# Etch-a-sketch.net
KiCad netlist of a schematic drawn in EAGLE
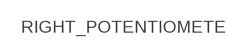
[diagram p0: schematic, sheet 1, part 1 of 2]
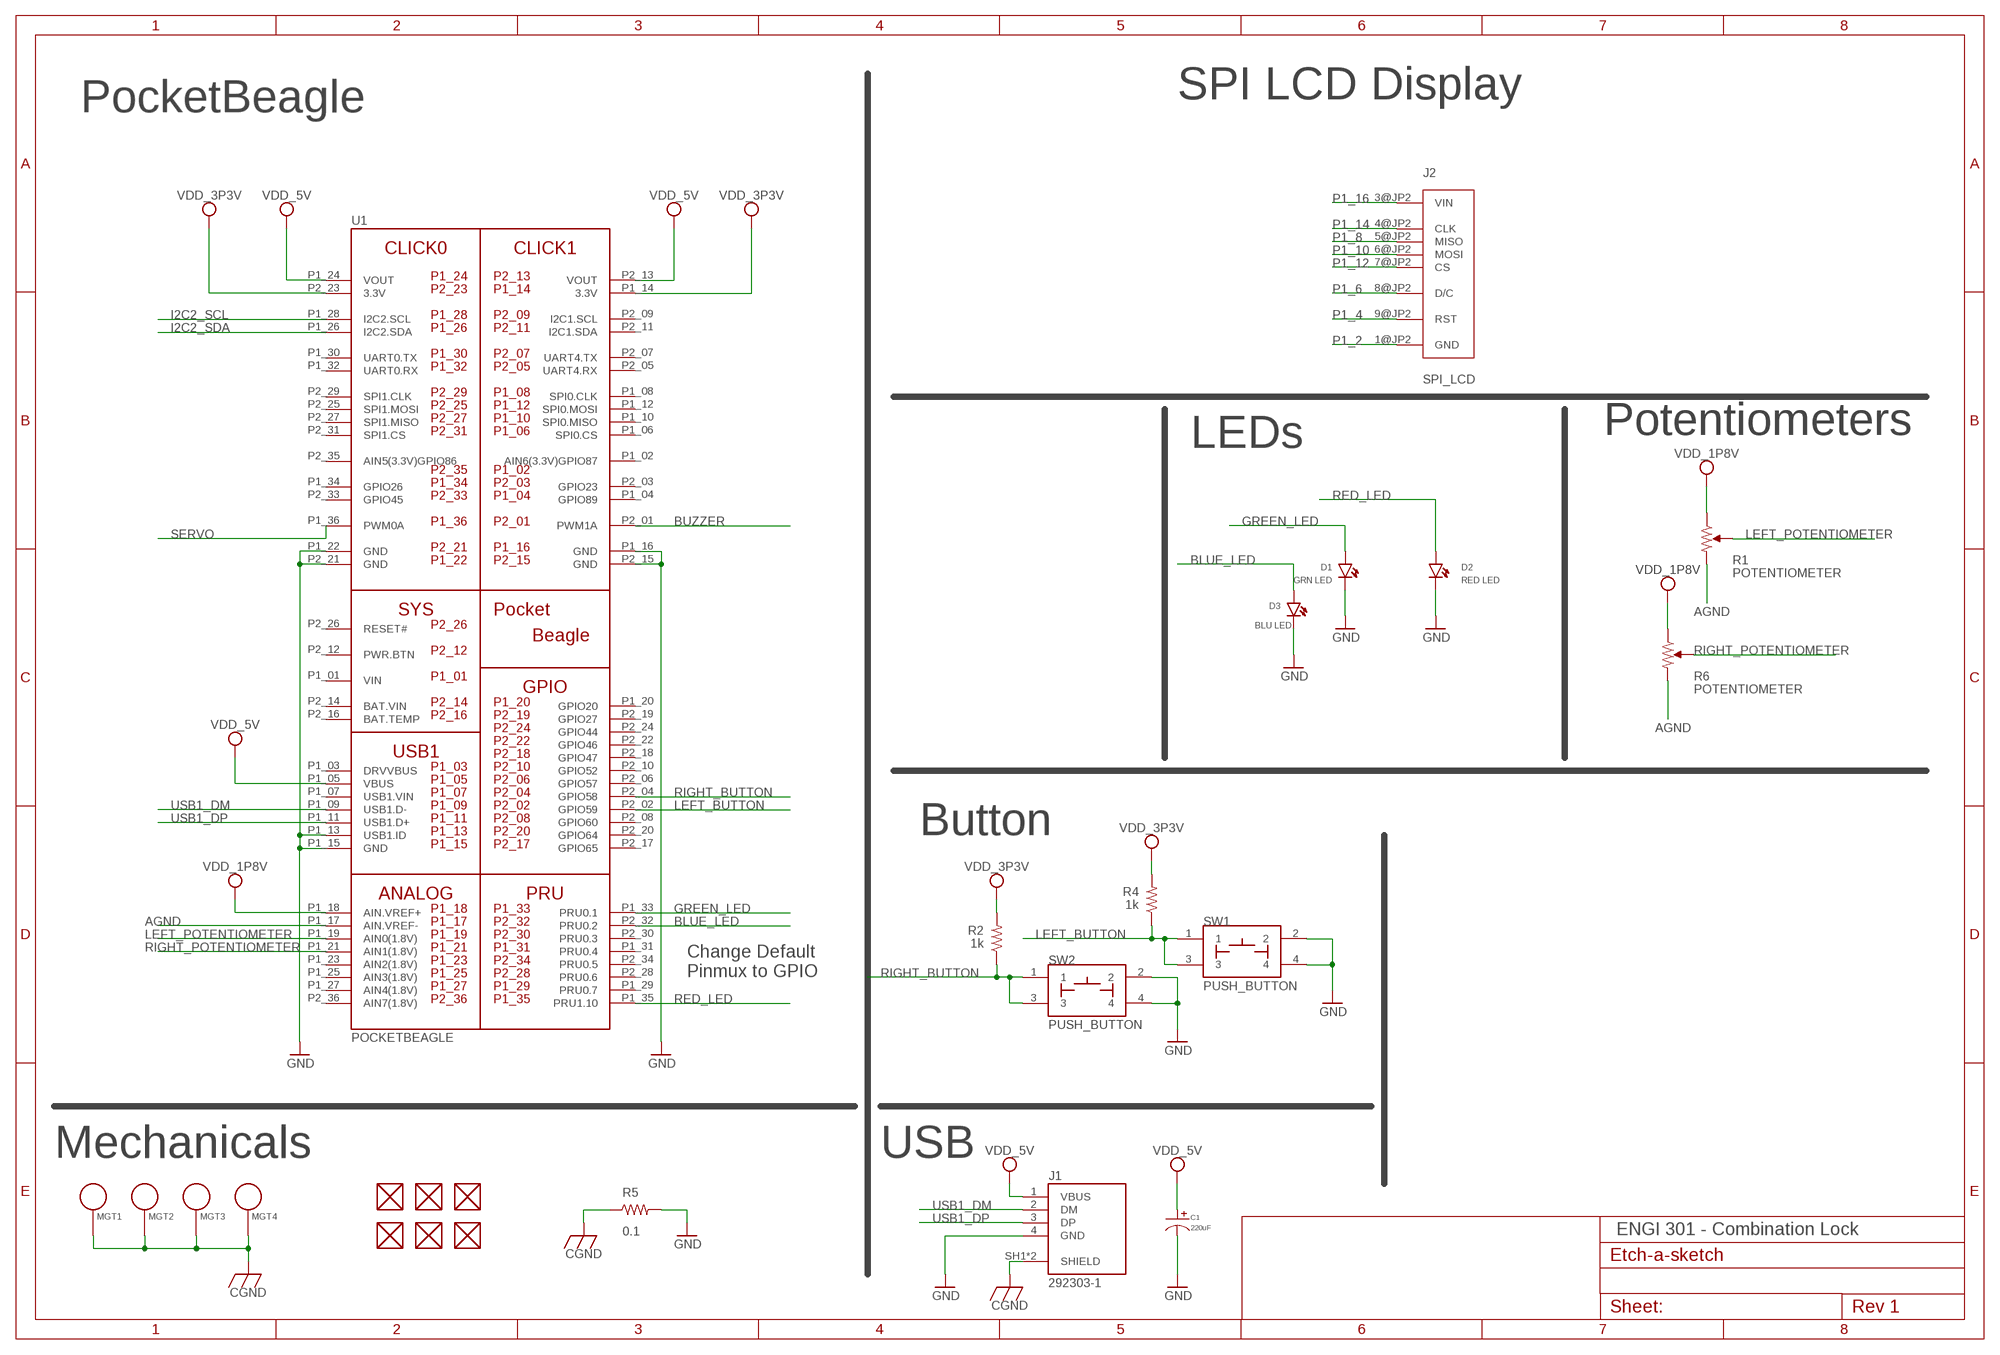
[diagram p1: schematic, sheet 1, part 2 of 2]

(export (version "E")
  (design (tool "Eeschema 10.0.6"))
  (components
    (comp (ref "C1")
      (value "220uF")
      (footprint "eagle-import:CP10MM")
      (libsource (lib "eagle-import") (part "CAPACITOR_P_10MM"))
    )
    (comp (ref "D1")
      (value "GRN LED")
      (footprint "eagle-import:EIA-STD")
      (libsource (lib "eagle-import") (part "LED"))
    )
    (comp (ref "D2")
      (value "RED LED")
      (footprint "eagle-import:EIA-STD")
      (libsource (lib "eagle-import") (part "LED"))
    )
    (comp (ref "D3")
      (value "GRN LED")
      (footprint "eagle-import:EIA-STD")
      (libsource (lib "eagle-import") (part "LED"))
    )
    (comp (ref "FUD1")
      (value "FIDUCIAL")
      (footprint "eagle-import:FIDUCIAL_40MIL")
      (libsource (lib "eagle-import") (part "FIDUCIAL"))
    )
    (comp (ref "FUD2")
      (value "FIDUCIAL")
      (footprint "eagle-import:FIDUCIAL_40MIL")
      (libsource (lib "eagle-import") (part "FIDUCIAL"))
    )
    (comp (ref "FUD3")
      (value "FIDUCIAL")
      (footprint "eagle-import:FIDUCIAL_40MIL")
      (libsource (lib "eagle-import") (part "FIDUCIAL"))
    )
    (comp (ref "FUD4")
      (value "FIDUCIAL")
      (footprint "eagle-import:FIDUCIAL_40MIL")
      (libsource (lib "eagle-import") (part "FIDUCIAL"))
    )
    (comp (ref "FUD5")
      (value "FIDUCIAL")
      (footprint "eagle-import:FIDUCIAL_40MIL")
      (libsource (lib "eagle-import") (part "FIDUCIAL"))
    )
    (comp (ref "FUD6")
      (value "FIDUCIAL")
      (footprint "eagle-import:FIDUCIAL_40MIL")
      (libsource (lib "eagle-import") (part "FIDUCIAL"))
    )
    (comp (ref "J1")
      (value "292303-1")
      (footprint "eagle-import:TE_292303-1")
      (fields (field (name "MF") "TE Connectivity"))
      (libsource (lib "eagle-import") (part "292303-1"))
    )
    (comp (ref "J2")
      (value "SPI_LCD")
      (footprint "eagle-import:TFT_LCD_PCB")
      (libsource (lib "eagle-import") (part "SPI_LCD"))
    )
    (comp (ref "MGT1")
      (value "MOUNTING_HOLE")
      (footprint "eagle-import:MOUNTING_HOLE")
      (libsource (lib "eagle-import") (part "MOUNTING_HOLE"))
    )
    (comp (ref "MGT2")
      (value "MOUNTING_HOLE")
      (footprint "eagle-import:MOUNTING_HOLE")
      (libsource (lib "eagle-import") (part "MOUNTING_HOLE"))
    )
    (comp (ref "MGT3")
      (value "MOUNTING_HOLE")
      (footprint "eagle-import:MOUNTING_HOLE")
      (libsource (lib "eagle-import") (part "MOUNTING_HOLE"))
    )
    (comp (ref "MGT4")
      (value "MOUNTING_HOLE")
      (footprint "eagle-import:MOUNTING_HOLE")
      (libsource (lib "eagle-import") (part "MOUNTING_HOLE"))
    )
    (comp (ref "R1")
      (value "POTENTIOMETER")
      (footprint "eagle-import:POT-PO90S")
      (libsource (lib "eagle-import") (part "POTENTIOMETER"))
    )
    (comp (ref "R2")
      (value "1k")
      (footprint "eagle-import:R0603")
      (libsource (lib "eagle-import") (part "R_R0603"))
    )
    (comp (ref "R4")
      (value "1k")
      (footprint "eagle-import:R0603")
      (libsource (lib "eagle-import") (part "R_R0603"))
    )
    (comp (ref "R5")
      (value "0.1")
      (footprint "eagle-import:R0805")
      (libsource (lib "eagle-import") (part "R_R0805"))
    )
    (comp (ref "R6")
      (value "POTENTIOMETER")
      (footprint "eagle-import:POT-PO90S")
      (libsource (lib "eagle-import") (part "POTENTIOMETER"))
    )
    (comp (ref "SW1")
      (value "PUSH_BUTTON")
      (footprint "eagle-import:BUTTON_12.5MM")
      (libsource (lib "eagle-import") (part "PUSH_BUTTON"))
    )
    (comp (ref "SW2")
      (value "PUSH_BUTTON")
      (footprint "eagle-import:BUTTON_12.5MM")
      (libsource (lib "eagle-import") (part "PUSH_BUTTON"))
    )
    (comp (ref "U1")
      (value "POCKETBEAGLE")
      (footprint "eagle-import:POCKETBEAGLE")
      (libsource (lib "eagle-import") (part "POCKETBEAGLE"))
    )
  )
  (nets
    (net (code "1") (name "/AGND") (class "Default")
      (node (ref "R1") (pin "CW") (pinfunction "CW_CW") (pintype "passive"))
      (node (ref "R6") (pin "CW") (pinfunction "CW_CW") (pintype "passive"))
      (node (ref "U1") (pin "P1_17") (pinfunction "AIN.VREF-_P1_17") (pintype "input"))
    )
    (net (code "2") (name "/BAT.VIN") (class "Default")
      (node (ref "U1") (pin "P2_14") (pinfunction "BAT.VIN_P2_14") (pintype "power_in"))
    )
    (net (code "3") (name "/BUZZER") (class "Default")
      (node (ref "U1") (pin "P2_01") (pinfunction "PWM1A_P2_01") (pintype "bidirectional"))
    )
    (net (code "4") (name "/GREEN_LED") (class "Default")
      (node (ref "D1") (pin "ANODE") (pinfunction "ANODE_ANODE") (pintype "bidirectional"))
      (node (ref "D3") (pin "ANODE") (pinfunction "ANODE_ANODE") (pintype "bidirectional"))
      (node (ref "U1") (pin "P1_33") (pinfunction "PRU0.1_P1_33") (pintype "bidirectional"))
    )
    (net (code "5") (name "/I2C2_SCL") (class "Default")
      (node (ref "U1") (pin "P1_28") (pinfunction "I2C2.SCL_P1_28") (pintype "bidirectional"))
    )
    (net (code "6") (name "/I2C2_SDA") (class "Default")
      (node (ref "U1") (pin "P1_26") (pinfunction "I2C2.SDA_P1_26") (pintype "bidirectional"))
    )
    (net (code "7") (name "/LEFT_BUTTON") (class "Default")
      (node (ref "R2") (pin "1") (pinfunction "1_1") (pintype "passive"))
      (node (ref "R4") (pin "1") (pinfunction "1_1") (pintype "passive"))
      (node (ref "SW1") (pin "1") (pinfunction "1_1") (pintype "bidirectional"))
      (node (ref "SW1") (pin "3") (pinfunction "3_3") (pintype "bidirectional"))
      (node (ref "SW2") (pin "1") (pinfunction "1_1") (pintype "bidirectional"))
      (node (ref "SW2") (pin "3") (pinfunction "3_3") (pintype "bidirectional"))
      (node (ref "U1") (pin "P2_02") (pinfunction "GPIO59_P2_02") (pintype "bidirectional"))
    )
    (net (code "8") (name "/LEFT_POTENTIOMETER") (class "Default")
      (node (ref "R1") (pin "S") (pinfunction "S_S") (pintype "bidirectional"))
      (node (ref "R6") (pin "S") (pinfunction "S_S") (pintype "bidirectional"))
      (node (ref "U1") (pin "P1_19") (pinfunction "AIN0(1.8V)_P1_19") (pintype "input"))
    )
    (net (code "9") (name "/RED_LED") (class "Default")
      (node (ref "D2") (pin "ANODE") (pinfunction "ANODE_ANODE") (pintype "bidirectional"))
      (node (ref "U1") (pin "P1_35") (pinfunction "PRU1.10_P1_35") (pintype "bidirectional"))
    )
    (net (code "10") (name "/SERVO") (class "Default")
      (node (ref "U1") (pin "P1_36") (pinfunction "PWM0A_P1_36") (pintype "bidirectional"))
    )
    (net (code "11") (name "/USB1_DM") (class "Default")
      (node (ref "J1") (pin "2") (pinfunction "DM_2") (pintype "passive"))
      (node (ref "U1") (pin "P1_09") (pinfunction "USB1.D-_P1_09") (pintype "bidirectional"))
    )
    (net (code "12") (name "/USB1_DP") (class "Default")
      (node (ref "J1") (pin "3") (pinfunction "DP_3") (pintype "passive"))
      (node (ref "U1") (pin "P1_11") (pinfunction "USB1.D+_P1_11") (pintype "bidirectional"))
    )
    (net (code "13") (name "/VIN") (class "Default")
      (node (ref "U1") (pin "P1_01") (pinfunction "VIN_P1_01") (pintype "power_in"))
    )
    (net (code "14") (name "CGND") (class "Default")
      (node (ref "J1") (pin "SH1") (pinfunction "SHIELD_SH1") (pintype "passive"))
      (node (ref "J1") (pin "SH2") (pinfunction "SHIELD_SH2") (pintype "passive"))
      (node (ref "MGT1") (pin "P$1") (pinfunction "P$1_P$1") (pintype "bidirectional"))
      (node (ref "MGT2") (pin "P$1") (pinfunction "P$1_P$1") (pintype "bidirectional"))
      (node (ref "MGT3") (pin "P$1") (pinfunction "P$1_P$1") (pintype "bidirectional"))
      (node (ref "MGT4") (pin "P$1") (pinfunction "P$1_P$1") (pintype "bidirectional"))
      (node (ref "R5") (pin "1") (pinfunction "1_1") (pintype "passive"))
    )
    (net (code "15") (name "GND") (class "Default")
      (node (ref "C1") (pin "P$2") (pinfunction "P$2_P$2") (pintype "passive"))
      (node (ref "D1") (pin "CATHODE") (pinfunction "CATHODE_CATHODE") (pintype "bidirectional"))
      (node (ref "D2") (pin "CATHODE") (pinfunction "CATHODE_CATHODE") (pintype "bidirectional"))
      (node (ref "D3") (pin "CATHODE") (pinfunction "CATHODE_CATHODE") (pintype "bidirectional"))
      (node (ref "J1") (pin "4") (pinfunction "GND_4") (pintype "passive"))
      (node (ref "R5") (pin "2") (pinfunction "2_2") (pintype "passive"))
      (node (ref "SW1") (pin "2") (pinfunction "2_2") (pintype "bidirectional"))
      (node (ref "SW1") (pin "4") (pinfunction "4_4") (pintype "bidirectional"))
      (node (ref "SW2") (pin "2") (pinfunction "2_2") (pintype "bidirectional"))
      (node (ref "SW2") (pin "4") (pinfunction "4_4") (pintype "bidirectional"))
      (node (ref "U1") (pin "P1_13") (pinfunction "USB1.ID_P1_13") (pintype "bidirectional"))
      (node (ref "U1") (pin "P1_15") (pinfunction "GND_P1_15") (pintype "bidirectional"))
      (node (ref "U1") (pin "P1_16") (pinfunction "GND_P1_16") (pintype "power_in"))
      (node (ref "U1") (pin "P1_22") (pinfunction "GND_P1_22") (pintype "power_in"))
      (node (ref "U1") (pin "P2_15") (pinfunction "GND_P2_15") (pintype "power_in"))
      (node (ref "U1") (pin "P2_21") (pinfunction "GND_P2_21") (pintype "power_in"))
    )
    (net (code "16") (name "VDD_1P8V") (class "Default")
      (node (ref "R1") (pin "CCW") (pinfunction "CCW_CCW") (pintype "passive"))
      (node (ref "R6") (pin "CCW") (pinfunction "CCW_CCW") (pintype "passive"))
      (node (ref "U1") (pin "P1_18") (pinfunction "AIN.VREF+_P1_18") (pintype "input"))
    )
    (net (code "17") (name "VDD_3P3V") (class "Default")
      (node (ref "R2") (pin "2") (pinfunction "2_2") (pintype "passive"))
      (node (ref "R4") (pin "2") (pinfunction "2_2") (pintype "passive"))
      (node (ref "U1") (pin "P1_14") (pinfunction "3.3V_P1_14") (pintype "power_in"))
      (node (ref "U1") (pin "P2_23") (pinfunction "3.3V_P2_23") (pintype "power_in"))
    )
    (net (code "18") (name "VDD_5V") (class "Default")
      (node (ref "C1") (pin "P$1") (pinfunction "P$1_P$1") (pintype "passive"))
      (node (ref "J1") (pin "1") (pinfunction "VBUS_1") (pintype "passive"))
      (node (ref "U1") (pin "P1_05") (pinfunction "VBUS_P1_05") (pintype "bidirectional"))
      (node (ref "U1") (pin "P1_24") (pinfunction "VOUT_P1_24") (pintype "power_in"))
      (node (ref "U1") (pin "P2_13") (pinfunction "VOUT_P2_13") (pintype "power_in"))
    )
    (net (code "19") (name "unconnected-(FUD1-PadP$1)") (class "Default")
      (node (ref "FUD1") (pin "P$1") (pinfunction "P$1_P$1") (pintype "no_connect"))
    )
    (net (code "20") (name "unconnected-(FUD2-PadP$1)") (class "Default")
      (node (ref "FUD2") (pin "P$1") (pinfunction "P$1_P$1") (pintype "no_connect"))
    )
    (net (code "21") (name "unconnected-(FUD3-PadP$1)") (class "Default")
      (node (ref "FUD3") (pin "P$1") (pinfunction "P$1_P$1") (pintype "no_connect"))
    )
    (net (code "22") (name "unconnected-(FUD4-PadP$1)") (class "Default")
      (node (ref "FUD4") (pin "P$1") (pinfunction "P$1_P$1") (pintype "no_connect"))
    )
    (net (code "23") (name "unconnected-(FUD5-PadP$1)") (class "Default")
      (node (ref "FUD5") (pin "P$1") (pinfunction "P$1_P$1") (pintype "no_connect"))
    )
    (net (code "24") (name "unconnected-(FUD6-PadP$1)") (class "Default")
      (node (ref "FUD6") (pin "P$1") (pinfunction "P$1_P$1") (pintype "no_connect"))
    )
    (net (code "25") (name "unconnected-(J2-CLK-Pad4@JP2)") (class "Default")
      (node (ref "J2") (pin "4@JP2") (pinfunction "CLK_4@JP2") (pintype "bidirectional"))
    )
    (net (code "26") (name "unconnected-(J2-CS-Pad7@JP2)") (class "Default")
      (node (ref "J2") (pin "7@JP2") (pinfunction "CS_7@JP2") (pintype "bidirectional"))
    )
    (net (code "27") (name "unconnected-(J2-D{slash}C-Pad8@JP2)") (class "Default")
      (node (ref "J2") (pin "8@JP2") (pinfunction "D/C_8@JP2") (pintype "bidirectional"))
    )
    (net (code "28") (name "unconnected-(J2-GND-Pad1@JP2)") (class "Default")
      (node (ref "J2") (pin "1@JP2") (pinfunction "GND_1@JP2") (pintype "bidirectional"))
    )
    (net (code "29") (name "unconnected-(J2-MISO-Pad5@JP2)") (class "Default")
      (node (ref "J2") (pin "5@JP2") (pinfunction "MISO_5@JP2") (pintype "bidirectional"))
    )
    (net (code "30") (name "unconnected-(J2-MOSI-Pad6@JP2)") (class "Default")
      (node (ref "J2") (pin "6@JP2") (pinfunction "MOSI_6@JP2") (pintype "bidirectional"))
    )
    (net (code "31") (name "unconnected-(J2-RST-Pad9@JP2)") (class "Default")
      (node (ref "J2") (pin "9@JP2") (pinfunction "RST_9@JP2") (pintype "bidirectional"))
    )
    (net (code "32") (name "unconnected-(J2-VIN-Pad3@JP2)") (class "Default")
      (node (ref "J2") (pin "3@JP2") (pinfunction "VIN_3@JP2") (pintype "bidirectional"))
    )
    (net (code "33") (name "unconnected-(U1-AIN1(1.8V)-PadP1_21)") (class "Default")
      (node (ref "U1") (pin "P1_21") (pinfunction "AIN1(1.8V)_P1_21") (pintype "input"))
    )
    (net (code "34") (name "unconnected-(U1-AIN2(1.8V)-PadP1_23)") (class "Default")
      (node (ref "U1") (pin "P1_23") (pinfunction "AIN2(1.8V)_P1_23") (pintype "input"))
    )
    (net (code "35") (name "unconnected-(U1-AIN3(1.8V)-PadP1_25)") (class "Default")
      (node (ref "U1") (pin "P1_25") (pinfunction "AIN3(1.8V)_P1_25") (pintype "input"))
    )
    (net (code "36") (name "unconnected-(U1-AIN4(1.8V)-PadP1_27)") (class "Default")
      (node (ref "U1") (pin "P1_27") (pinfunction "AIN4(1.8V)_P1_27") (pintype "input"))
    )
    (net (code "37") (name "unconnected-(U1-AIN5(3.3V)GPIO86-PadP2_35)") (class "Default")
      (node (ref "U1") (pin "P2_35") (pinfunction "AIN5(3.3V)GPIO86_P2_35") (pintype "bidirectional"))
    )
    (net (code "38") (name "unconnected-(U1-AIN6(3.3V)GPIO87-PadP1_02)") (class "Default")
      (node (ref "U1") (pin "P1_02") (pinfunction "AIN6(3.3V)GPIO87_P1_02") (pintype "bidirectional"))
    )
    (net (code "39") (name "unconnected-(U1-AIN7(1.8V)-PadP2_36)") (class "Default")
      (node (ref "U1") (pin "P2_36") (pinfunction "AIN7(1.8V)_P2_36") (pintype "input"))
    )
    (net (code "40") (name "unconnected-(U1-BAT.TEMP-PadP2_16)") (class "Default")
      (node (ref "U1") (pin "P2_16") (pinfunction "BAT.TEMP_P2_16") (pintype "input"))
    )
    (net (code "41") (name "unconnected-(U1-DRVVBUS-PadP1_03)") (class "Default")
      (node (ref "U1") (pin "P1_03") (pinfunction "DRVVBUS_P1_03") (pintype "bidirectional"))
    )
    (net (code "42") (name "unconnected-(U1-GPIO20-PadP1_20)") (class "Default")
      (node (ref "U1") (pin "P1_20") (pinfunction "GPIO20_P1_20") (pintype "bidirectional"))
    )
    (net (code "43") (name "unconnected-(U1-GPIO23-PadP2_03)") (class "Default")
      (node (ref "U1") (pin "P2_03") (pinfunction "GPIO23_P2_03") (pintype "bidirectional"))
    )
    (net (code "44") (name "unconnected-(U1-GPIO26-PadP1_34)") (class "Default")
      (node (ref "U1") (pin "P1_34") (pinfunction "GPIO26_P1_34") (pintype "bidirectional"))
    )
    (net (code "45") (name "unconnected-(U1-GPIO27-PadP2_19)") (class "Default")
      (node (ref "U1") (pin "P2_19") (pinfunction "GPIO27_P2_19") (pintype "bidirectional"))
    )
    (net (code "46") (name "unconnected-(U1-GPIO44-PadP2_24)") (class "Default")
      (node (ref "U1") (pin "P2_24") (pinfunction "GPIO44_P2_24") (pintype "bidirectional"))
    )
    (net (code "47") (name "unconnected-(U1-GPIO45-PadP2_33)") (class "Default")
      (node (ref "U1") (pin "P2_33") (pinfunction "GPIO45_P2_33") (pintype "bidirectional"))
    )
    (net (code "48") (name "unconnected-(U1-GPIO46-PadP2_22)") (class "Default")
      (node (ref "U1") (pin "P2_22") (pinfunction "GPIO46_P2_22") (pintype "bidirectional"))
    )
    (net (code "49") (name "unconnected-(U1-GPIO47-PadP2_18)") (class "Default")
      (node (ref "U1") (pin "P2_18") (pinfunction "GPIO47_P2_18") (pintype "bidirectional"))
    )
    (net (code "50") (name "unconnected-(U1-GPIO52-PadP2_10)") (class "Default")
      (node (ref "U1") (pin "P2_10") (pinfunction "GPIO52_P2_10") (pintype "bidirectional"))
    )
    (net (code "51") (name "unconnected-(U1-GPIO57-PadP2_06)") (class "Default")
      (node (ref "U1") (pin "P2_06") (pinfunction "GPIO57_P2_06") (pintype "bidirectional"))
    )
    (net (code "52") (name "unconnected-(U1-GPIO58-PadP2_04)") (class "Default")
      (node (ref "U1") (pin "P2_04") (pinfunction "GPIO58_P2_04") (pintype "bidirectional"))
    )
    (net (code "53") (name "unconnected-(U1-GPIO60-PadP2_08)") (class "Default")
      (node (ref "U1") (pin "P2_08") (pinfunction "GPIO60_P2_08") (pintype "bidirectional"))
    )
    (net (code "54") (name "unconnected-(U1-GPIO64-PadP2_20)") (class "Default")
      (node (ref "U1") (pin "P2_20") (pinfunction "GPIO64_P2_20") (pintype "bidirectional"))
    )
    (net (code "55") (name "unconnected-(U1-GPIO65-PadP2_17)") (class "Default")
      (node (ref "U1") (pin "P2_17") (pinfunction "GPIO65_P2_17") (pintype "bidirectional"))
    )
    (net (code "56") (name "unconnected-(U1-GPIO89-PadP1_04)") (class "Default")
      (node (ref "U1") (pin "P1_04") (pinfunction "GPIO89_P1_04") (pintype "bidirectional"))
    )
    (net (code "57") (name "unconnected-(U1-I2C1.SCL-PadP2_09)") (class "Default")
      (node (ref "U1") (pin "P2_09") (pinfunction "I2C1.SCL_P2_09") (pintype "bidirectional"))
    )
    (net (code "58") (name "unconnected-(U1-I2C1.SDA-PadP2_11)") (class "Default")
      (node (ref "U1") (pin "P2_11") (pinfunction "I2C1.SDA_P2_11") (pintype "bidirectional"))
    )
    (net (code "59") (name "unconnected-(U1-PRU0.2-PadP2_32)") (class "Default")
      (node (ref "U1") (pin "P2_32") (pinfunction "PRU0.2_P2_32") (pintype "bidirectional"))
    )
    (net (code "60") (name "unconnected-(U1-PRU0.3-PadP2_30)") (class "Default")
      (node (ref "U1") (pin "P2_30") (pinfunction "PRU0.3_P2_30") (pintype "bidirectional"))
    )
    (net (code "61") (name "unconnected-(U1-PRU0.4-PadP1_31)") (class "Default")
      (node (ref "U1") (pin "P1_31") (pinfunction "PRU0.4_P1_31") (pintype "bidirectional"))
    )
    (net (code "62") (name "unconnected-(U1-PRU0.5-PadP2_34)") (class "Default")
      (node (ref "U1") (pin "P2_34") (pinfunction "PRU0.5_P2_34") (pintype "bidirectional"))
    )
    (net (code "63") (name "unconnected-(U1-PRU0.6-PadP2_28)") (class "Default")
      (node (ref "U1") (pin "P2_28") (pinfunction "PRU0.6_P2_28") (pintype "bidirectional"))
    )
    (net (code "64") (name "unconnected-(U1-PRU0.7-PadP1_29)") (class "Default")
      (node (ref "U1") (pin "P1_29") (pinfunction "PRU0.7_P1_29") (pintype "bidirectional"))
    )
    (net (code "65") (name "unconnected-(U1-PWR.BTN-PadP2_12)") (class "Default")
      (node (ref "U1") (pin "P2_12") (pinfunction "PWR.BTN_P2_12") (pintype "input"))
    )
    (net (code "66") (name "unconnected-(U1-RESET#-PadP2_26)") (class "Default")
      (node (ref "U1") (pin "P2_26") (pinfunction "RESET#_P2_26") (pintype "input"))
    )
    (net (code "67") (name "unconnected-(U1-SPI0.CLK-PadP1_08)") (class "Default")
      (node (ref "U1") (pin "P1_08") (pinfunction "SPI0.CLK_P1_08") (pintype "bidirectional"))
    )
    (net (code "68") (name "unconnected-(U1-SPI0.CS-PadP1_06)") (class "Default")
      (node (ref "U1") (pin "P1_06") (pinfunction "SPI0.CS_P1_06") (pintype "bidirectional"))
    )
    (net (code "69") (name "unconnected-(U1-SPI0.MISO-PadP1_10)") (class "Default")
      (node (ref "U1") (pin "P1_10") (pinfunction "SPI0.MISO_P1_10") (pintype "bidirectional"))
    )
    (net (code "70") (name "unconnected-(U1-SPI0.MOSI-PadP1_12)") (class "Default")
      (node (ref "U1") (pin "P1_12") (pinfunction "SPI0.MOSI_P1_12") (pintype "bidirectional"))
    )
    (net (code "71") (name "unconnected-(U1-SPI1.CLK-PadP2_29)") (class "Default")
      (node (ref "U1") (pin "P2_29") (pinfunction "SPI1.CLK_P2_29") (pintype "bidirectional"))
    )
    (net (code "72") (name "unconnected-(U1-SPI1.CS-PadP2_31)") (class "Default")
      (node (ref "U1") (pin "P2_31") (pinfunction "SPI1.CS_P2_31") (pintype "bidirectional"))
    )
    (net (code "73") (name "unconnected-(U1-SPI1.MISO-PadP2_27)") (class "Default")
      (node (ref "U1") (pin "P2_27") (pinfunction "SPI1.MISO_P2_27") (pintype "bidirectional"))
    )
    (net (code "74") (name "unconnected-(U1-SPI1.MOSI-PadP2_25)") (class "Default")
      (node (ref "U1") (pin "P2_25") (pinfunction "SPI1.MOSI_P2_25") (pintype "bidirectional"))
    )
    (net (code "75") (name "unconnected-(U1-UART0.RX-PadP1_32)") (class "Default")
      (node (ref "U1") (pin "P1_32") (pinfunction "UART0.RX_P1_32") (pintype "bidirectional"))
    )
    (net (code "76") (name "unconnected-(U1-UART0.TX-PadP1_30)") (class "Default")
      (node (ref "U1") (pin "P1_30") (pinfunction "UART0.TX_P1_30") (pintype "bidirectional"))
    )
    (net (code "77") (name "unconnected-(U1-UART4.RX-PadP2_05)") (class "Default")
      (node (ref "U1") (pin "P2_05") (pinfunction "UART4.RX_P2_05") (pintype "bidirectional"))
    )
    (net (code "78") (name "unconnected-(U1-UART4.TX-PadP2_07)") (class "Default")
      (node (ref "U1") (pin "P2_07") (pinfunction "UART4.TX_P2_07") (pintype "bidirectional"))
    )
    (net (code "79") (name "unconnected-(U1-USB1.VIN-PadP1_07)") (class "Default")
      (node (ref "U1") (pin "P1_07") (pinfunction "USB1.VIN_P1_07") (pintype "bidirectional"))
    )
  )
)
